# mini_exp_v1-1-0b.net
KiCad netlist of a schematic drawn in EAGLE
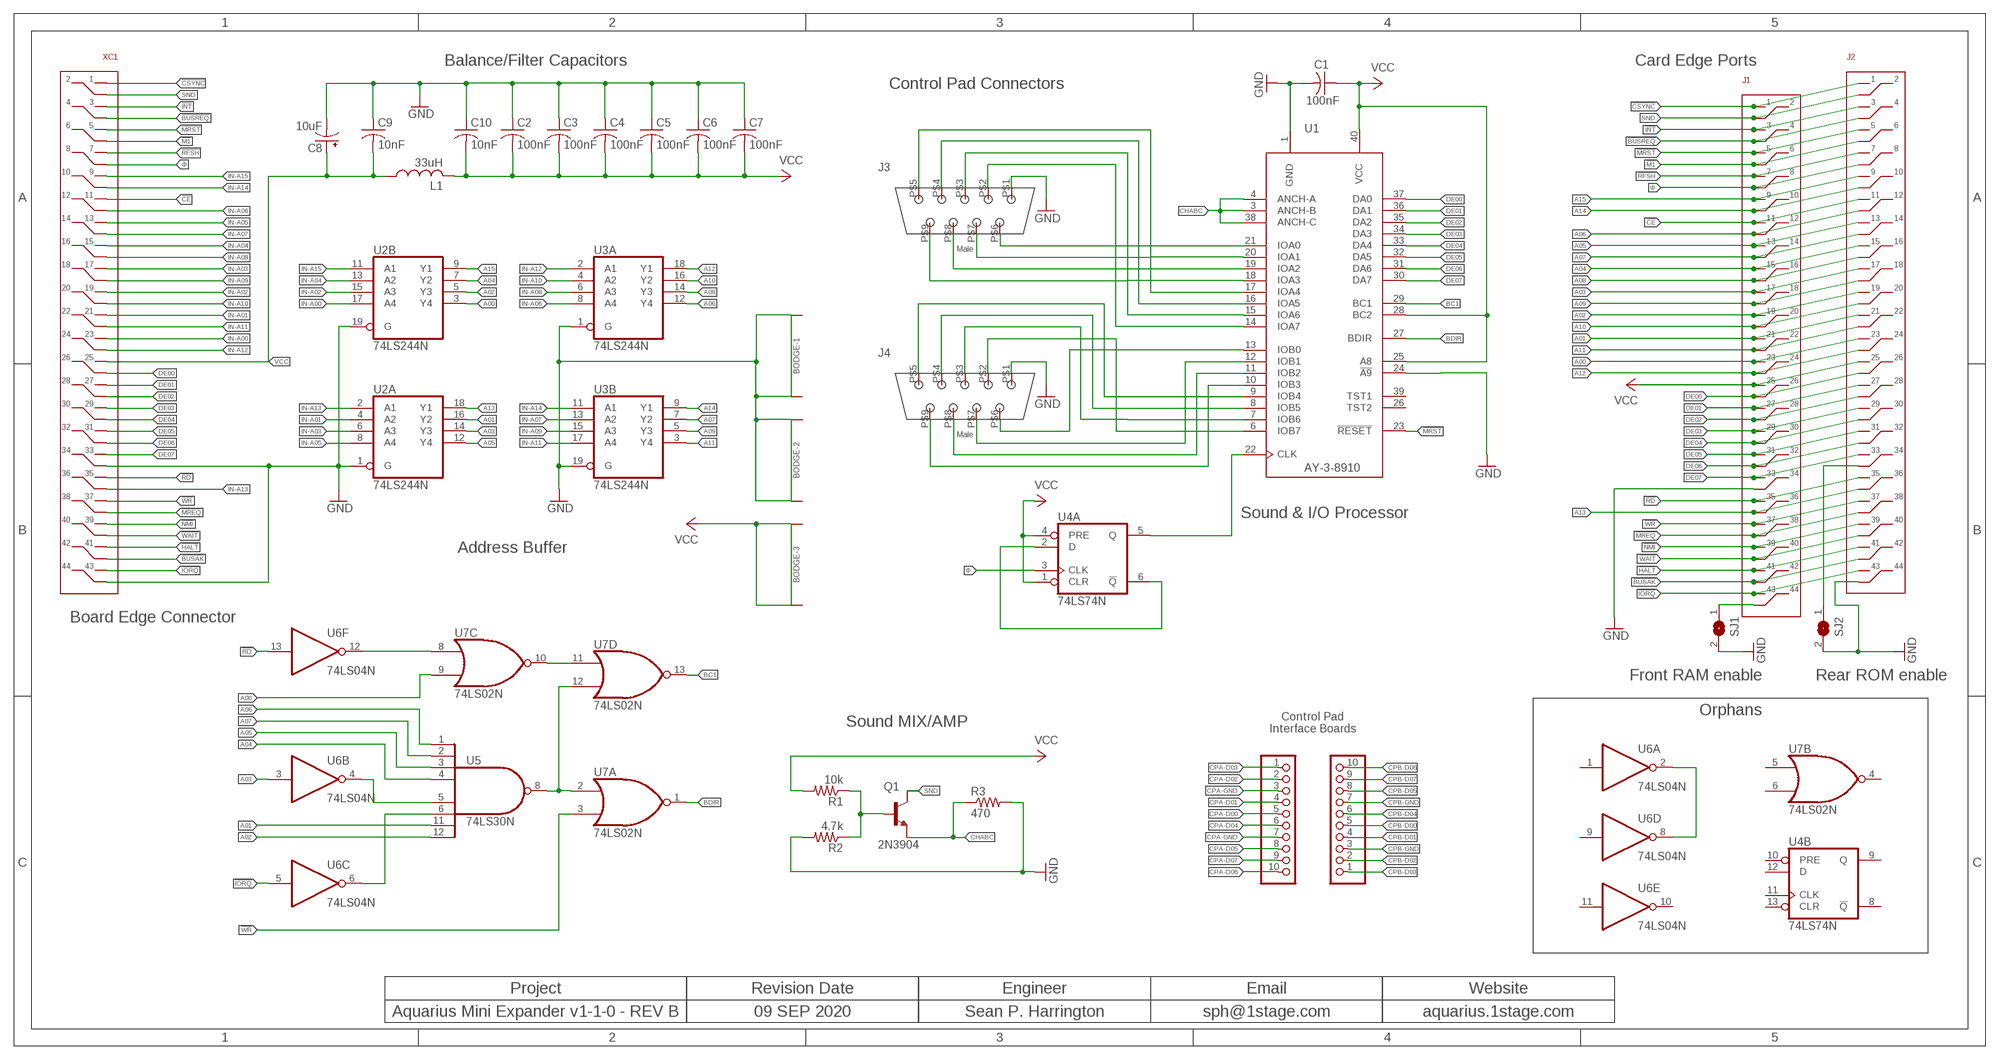
[diagram p0: schematic, sheet 1]

(export (version "E")
  (design (tool "Eeschema 10.0.6"))
  (components
    (comp (ref "C1")
      (value "100nF")
      (footprint "eagle-import:C050-025X095")
      (libsource (lib "eagle-import") (part "C-US050-025X095"))
    )
    (comp (ref "C2")
      (value "100nF")
      (footprint "eagle-import:C050-025X095")
      (libsource (lib "eagle-import") (part "C-US050-025X095"))
    )
    (comp (ref "C3")
      (value "100nF")
      (footprint "eagle-import:C050-025X095")
      (libsource (lib "eagle-import") (part "C-US050-025X095"))
    )
    (comp (ref "C4")
      (value "100nF")
      (footprint "eagle-import:C050-025X095")
      (libsource (lib "eagle-import") (part "C-US050-025X095"))
    )
    (comp (ref "C5")
      (value "100nF")
      (footprint "eagle-import:C050-025X095")
      (libsource (lib "eagle-import") (part "C-US050-025X095"))
    )
    (comp (ref "C6")
      (value "100nF")
      (footprint "eagle-import:C050-025X095")
      (libsource (lib "eagle-import") (part "C-US050-025X095"))
    )
    (comp (ref "C7")
      (value "100nF")
      (footprint "eagle-import:C050-025X095")
      (libsource (lib "eagle-import") (part "C-US050-025X095"))
    )
    (comp (ref "C8")
      (value "10uF")
      (footprint "eagle-import:E22-6")
      (libsource (lib "eagle-import") (part "CPOL-USE22-6AXIAL"))
    )
    (comp (ref "C9")
      (value "10nF")
      (footprint "eagle-import:C075-032X103")
      (libsource (lib "eagle-import") (part "C-US075-032X103"))
    )
    (comp (ref "C10")
      (value "10nF")
      (footprint "eagle-import:C075-032X103")
      (libsource (lib "eagle-import") (part "C-US075-032X103"))
    )
    (comp (ref "J1")
      (value "CR22A-44D-2.54DS(70)STRAIGHT")
      (footprint "eagle-import:CR22A-44D-2.54DS(70)")
      (libsource (lib "eagle-import") (part "CR22A-44D-2.54DS(70)STRAIGHT"))
    )
    (comp (ref "J2")
      (value "CR22A-44D-2.54DS(70)STRAIGHT")
      (footprint "eagle-import:CR22A-44D-2.54DS(70)")
      (libsource (lib "eagle-import") (part "CR22A-44D-2.54DS(70)STRAIGHT"))
    )
    (comp (ref "J3")
      (value "DB9-MALE-RA")
      (footprint "eagle-import:DB9-MALE-RA")
      (libsource (lib "eagle-import") (part "DB9-MALE-RA"))
    )
    (comp (ref "J4")
      (value "DB9-MALE-RA")
      (footprint "eagle-import:DB9-MALE-RA")
      (libsource (lib "eagle-import") (part "DB9-MALE-RA"))
    )
    (comp (ref "JP1")
      (value "PINHD-1X10")
      (footprint "eagle-import:1X10")
      (libsource (lib "eagle-import") (part "PINHD-1X10"))
    )
    (comp (ref "JP2")
      (value "PINHD-1X10")
      (footprint "eagle-import:1X10")
      (libsource (lib "eagle-import") (part "PINHD-1X10"))
    )
    (comp (ref "L1")
      (value "33uH")
      (footprint "eagle-import:0204_5")
      (libsource (lib "eagle-import") (part "L-US0204/5"))
    )
    (comp (ref "Q1")
      (value "2N3904")
      (footprint "eagle-import:TO92")
      (libsource (lib "eagle-import") (part "2N3904"))
    )
    (comp (ref "R1")
      (value "10k")
      (footprint "eagle-import:0207_7")
      (libsource (lib "eagle-import") (part "R-US_0207/7"))
    )
    (comp (ref "R2")
      (value "4.7k")
      (footprint "eagle-import:0207_7")
      (libsource (lib "eagle-import") (part "R-US_0207/7"))
    )
    (comp (ref "R3")
      (value "470")
      (footprint "eagle-import:0207_7")
      (libsource (lib "eagle-import") (part "R-US_0207/7"))
    )
    (comp (ref "SJ1") (value "SJ") (footprint "eagle-import:SJ") (libsource (lib "eagle-import") (part "SJ")))
    (comp (ref "SJ2") (value "SJ") (footprint "eagle-import:SJ") (libsource (lib "eagle-import") (part "SJ")))
    (comp (ref "U1")
      (value "AY-3-8910")
      (footprint "eagle-import:RAD38910-DIL40-6")
      (libsource (lib "eagle-import") (part "RAD38910DIL40-6"))
    )
    (comp (ref "U2")
      (value "74LS244N")
      (footprint "eagle-import:DIL20")
      (libsource (lib "eagle-import") (part "74244NLS"))
    )
    (comp (ref "U3")
      (value "74LS244N")
      (footprint "eagle-import:DIL20")
      (libsource (lib "eagle-import") (part "74244NLS"))
    )
    (comp (ref "U4")
      (value "74LS74N")
      (footprint "eagle-import:DIL14")
      (libsource (lib "eagle-import") (part "7474NLS"))
    )
    (comp (ref "U5")
      (value "74LS30N")
      (footprint "eagle-import:DIL14")
      (libsource (lib "eagle-import") (part "7430NLS"))
    )
    (comp (ref "U6")
      (value "74LS04N")
      (footprint "eagle-import:DIL14")
      (libsource (lib "eagle-import") (part "7404NLS"))
    )
    (comp (ref "U7")
      (value "74LS02N")
      (footprint "eagle-import:DIL14")
      (libsource (lib "eagle-import") (part "7402NLS"))
    )
    (comp (ref "XC1")
      (value "AQ-CART-EDGE")
      (footprint "eagle-import:AQ-CART-EDGE")
      (libsource (lib "eagle-import") (part "AQ-CART-EDGE"))
    )
    (comp (ref "XX01")
      (value "AQ-MX-BODGE-1")
      (footprint "eagle-import:AQ-MX-BODGE-1")
      (libsource (lib "eagle-import") (part "AQ-MX-BODGE-1"))
    )
    (comp (ref "XX02")
      (value "AQ-MX-BODGE-2")
      (footprint "eagle-import:AQ-MX-BODGE-2")
      (libsource (lib "eagle-import") (part "AQ-MX-BODGE-2"))
    )
    (comp (ref "XX03")
      (value "AQ-MX-BODGE-3")
      (footprint "eagle-import:AQ-MX-BODGE-3")
      (libsource (lib "eagle-import") (part "AQ-MX-BODGE-3"))
    )
  )
  (nets
    (net (code "1") (name "/~{BUSAK}") (class "Default")
      (node (ref "J1") (pin "P$42") (pinfunction "X42_P$42") (pintype "bidirectional"))
      (node (ref "J2") (pin "P$42") (pinfunction "X42_P$42") (pintype "bidirectional"))
      (node (ref "XC1") (pin "P$42") (pinfunction "X42_P$42") (pintype "bidirectional"))
    )
    (net (code "2") (name "/~{BUSREQ}") (class "Default")
      (node (ref "J1") (pin "P$4") (pinfunction "X4_P$4") (pintype "bidirectional"))
      (node (ref "J2") (pin "P$4") (pinfunction "X4_P$4") (pintype "bidirectional"))
      (node (ref "XC1") (pin "P$4") (pinfunction "X4_P$4") (pintype "bidirectional"))
    )
    (net (code "3") (name "/~{CE}") (class "Default")
      (node (ref "J1") (pin "P$11") (pinfunction "X11_P$11") (pintype "bidirectional"))
      (node (ref "J2") (pin "P$11") (pinfunction "X11_P$11") (pintype "bidirectional"))
      (node (ref "XC1") (pin "P$11") (pinfunction "X11_P$11") (pintype "bidirectional"))
    )
    (net (code "4") (name "/~{CSYNC}") (class "Default")
      (node (ref "J1") (pin "P$1") (pinfunction "X1_P$1") (pintype "bidirectional"))
      (node (ref "J2") (pin "P$1") (pinfunction "X1_P$1") (pintype "bidirectional"))
      (node (ref "XC1") (pin "P$1") (pinfunction "X1_P$1") (pintype "bidirectional"))
    )
    (net (code "5") (name "/~{HALT}") (class "Default")
      (node (ref "J1") (pin "P$41") (pinfunction "X41_P$41") (pintype "bidirectional"))
      (node (ref "J2") (pin "P$41") (pinfunction "X41_P$41") (pintype "bidirectional"))
      (node (ref "XC1") (pin "P$41") (pinfunction "X41_P$41") (pintype "bidirectional"))
    )
    (net (code "6") (name "/~{INT}") (class "Default")
      (node (ref "J1") (pin "P$3") (pinfunction "X3_P$3") (pintype "bidirectional"))
      (node (ref "J2") (pin "P$3") (pinfunction "X3_P$3") (pintype "bidirectional"))
      (node (ref "XC1") (pin "P$3") (pinfunction "X3_P$3") (pintype "bidirectional"))
    )
    (net (code "7") (name "/~{IORQ}") (class "Default")
      (node (ref "J1") (pin "P$43") (pinfunction "X43_P$43") (pintype "bidirectional"))
      (node (ref "J2") (pin "P$43") (pinfunction "X43_P$43") (pintype "bidirectional"))
      (node (ref "U6") (pin "5") (pinfunction "I_5") (pintype "input"))
      (node (ref "XC1") (pin "P$43") (pinfunction "X43_P$43") (pintype "bidirectional"))
    )
    (net (code "8") (name "/~{M1}") (class "Default")
      (node (ref "J1") (pin "P$6") (pinfunction "X6_P$6") (pintype "bidirectional"))
      (node (ref "J2") (pin "P$6") (pinfunction "X6_P$6") (pintype "bidirectional"))
      (node (ref "XC1") (pin "P$6") (pinfunction "X6_P$6") (pintype "bidirectional"))
    )
    (net (code "9") (name "/~{MREQ}") (class "Default")
      (node (ref "J1") (pin "P$38") (pinfunction "X38_P$38") (pintype "bidirectional"))
      (node (ref "J2") (pin "P$38") (pinfunction "X38_P$38") (pintype "bidirectional"))
      (node (ref "XC1") (pin "P$38") (pinfunction "X38_P$38") (pintype "bidirectional"))
    )
    (net (code "10") (name "/~{MRST}") (class "Default")
      (node (ref "J1") (pin "P$5") (pinfunction "X5_P$5") (pintype "bidirectional"))
      (node (ref "J2") (pin "P$5") (pinfunction "X5_P$5") (pintype "bidirectional"))
      (node (ref "U1") (pin "23") (pinfunction "~{RESET}_23") (pintype "bidirectional"))
      (node (ref "XC1") (pin "P$5") (pinfunction "X5_P$5") (pintype "bidirectional"))
    )
    (net (code "11") (name "/~{NMI}") (class "Default")
      (node (ref "J1") (pin "P$39") (pinfunction "X39_P$39") (pintype "bidirectional"))
      (node (ref "J2") (pin "P$39") (pinfunction "X39_P$39") (pintype "bidirectional"))
      (node (ref "XC1") (pin "P$39") (pinfunction "X39_P$39") (pintype "bidirectional"))
    )
    (net (code "12") (name "/~{RD}") (class "Default")
      (node (ref "J1") (pin "P$35") (pinfunction "X35_P$35") (pintype "bidirectional"))
      (node (ref "J2") (pin "P$35") (pinfunction "X35_P$35") (pintype "bidirectional"))
      (node (ref "U6") (pin "13") (pinfunction "I_13") (pintype "input"))
      (node (ref "XC1") (pin "P$35") (pinfunction "X35_P$35") (pintype "bidirectional"))
    )
    (net (code "13") (name "/~{RFSH}") (class "Default")
      (node (ref "J1") (pin "P$7") (pinfunction "X7_P$7") (pintype "bidirectional"))
      (node (ref "J2") (pin "P$7") (pinfunction "X7_P$7") (pintype "bidirectional"))
      (node (ref "XC1") (pin "P$7") (pinfunction "X7_P$7") (pintype "bidirectional"))
    )
    (net (code "14") (name "/~{WAIT}") (class "Default")
      (node (ref "J1") (pin "P$40") (pinfunction "X40_P$40") (pintype "bidirectional"))
      (node (ref "J2") (pin "P$40") (pinfunction "X40_P$40") (pintype "bidirectional"))
      (node (ref "XC1") (pin "P$40") (pinfunction "X40_P$40") (pintype "bidirectional"))
    )
    (net (code "15") (name "/~{WR}") (class "Default")
      (node (ref "J1") (pin "P$37") (pinfunction "X37_P$37") (pintype "bidirectional"))
      (node (ref "J2") (pin "P$37") (pinfunction "X37_P$37") (pintype "bidirectional"))
      (node (ref "U7") (pin "3") (pinfunction "I1_3") (pintype "input"))
      (node (ref "XC1") (pin "P$37") (pinfunction "X37_P$37") (pintype "bidirectional"))
    )
    (net (code "16") (name "A00") (class "Default")
      (node (ref "J1") (pin "P$23") (pinfunction "X23_P$23") (pintype "bidirectional"))
      (node (ref "J2") (pin "P$23") (pinfunction "X23_P$23") (pintype "bidirectional"))
      (node (ref "U2") (pin "3") (pinfunction "Y4_3") (pintype "tri_state"))
      (node (ref "U7") (pin "9") (pinfunction "I1_9") (pintype "input"))
    )
    (net (code "17") (name "A01") (class "Default")
      (node (ref "J1") (pin "P$21") (pinfunction "X21_P$21") (pintype "bidirectional"))
      (node (ref "J2") (pin "P$21") (pinfunction "X21_P$21") (pintype "bidirectional"))
      (node (ref "U2") (pin "16") (pinfunction "Y2_16") (pintype "tri_state"))
      (node (ref "U5") (pin "11") (pinfunction "I6_11") (pintype "input"))
    )
    (net (code "18") (name "A02") (class "Default")
      (node (ref "J1") (pin "P$19") (pinfunction "X19_P$19") (pintype "bidirectional"))
      (node (ref "J2") (pin "P$19") (pinfunction "X19_P$19") (pintype "bidirectional"))
      (node (ref "U2") (pin "5") (pinfunction "Y3_5") (pintype "tri_state"))
      (node (ref "U5") (pin "12") (pinfunction "I7_12") (pintype "input"))
    )
    (net (code "19") (name "A03") (class "Default")
      (node (ref "J1") (pin "P$17") (pinfunction "X17_P$17") (pintype "bidirectional"))
      (node (ref "J2") (pin "P$17") (pinfunction "X17_P$17") (pintype "bidirectional"))
      (node (ref "U2") (pin "14") (pinfunction "Y3_14") (pintype "tri_state"))
      (node (ref "U6") (pin "3") (pinfunction "I_3") (pintype "input"))
    )
    (net (code "20") (name "A04") (class "Default")
      (node (ref "J1") (pin "P$15") (pinfunction "X15_P$15") (pintype "bidirectional"))
      (node (ref "J2") (pin "P$15") (pinfunction "X15_P$15") (pintype "bidirectional"))
      (node (ref "U2") (pin "7") (pinfunction "Y2_7") (pintype "tri_state"))
      (node (ref "U5") (pin "4") (pinfunction "I3_4") (pintype "input"))
    )
    (net (code "21") (name "A05") (class "Default")
      (node (ref "J1") (pin "P$13") (pinfunction "X13_P$13") (pintype "bidirectional"))
      (node (ref "J2") (pin "P$13") (pinfunction "X13_P$13") (pintype "bidirectional"))
      (node (ref "U2") (pin "12") (pinfunction "Y4_12") (pintype "tri_state"))
      (node (ref "U5") (pin "3") (pinfunction "I2_3") (pintype "input"))
    )
    (net (code "22") (name "A06") (class "Default")
      (node (ref "J1") (pin "P$12") (pinfunction "X12_P$12") (pintype "bidirectional"))
      (node (ref "J2") (pin "P$12") (pinfunction "X12_P$12") (pintype "bidirectional"))
      (node (ref "U3") (pin "12") (pinfunction "Y4_12") (pintype "tri_state"))
      (node (ref "U5") (pin "1") (pinfunction "I0_1") (pintype "input"))
    )
    (net (code "23") (name "A07") (class "Default")
      (node (ref "J1") (pin "P$14") (pinfunction "X14_P$14") (pintype "bidirectional"))
      (node (ref "J2") (pin "P$14") (pinfunction "X14_P$14") (pintype "bidirectional"))
      (node (ref "U3") (pin "7") (pinfunction "Y2_7") (pintype "tri_state"))
      (node (ref "U5") (pin "2") (pinfunction "I1_2") (pintype "input"))
    )
    (net (code "24") (name "A08") (class "Default")
      (node (ref "J1") (pin "P$16") (pinfunction "X16_P$16") (pintype "bidirectional"))
      (node (ref "J2") (pin "P$16") (pinfunction "X16_P$16") (pintype "bidirectional"))
      (node (ref "U3") (pin "14") (pinfunction "Y3_14") (pintype "tri_state"))
    )
    (net (code "25") (name "A09") (class "Default")
      (node (ref "J1") (pin "P$18") (pinfunction "X18_P$18") (pintype "bidirectional"))
      (node (ref "J2") (pin "P$18") (pinfunction "X18_P$18") (pintype "bidirectional"))
      (node (ref "U3") (pin "5") (pinfunction "Y3_5") (pintype "tri_state"))
    )
    (net (code "26") (name "A10") (class "Default")
      (node (ref "J1") (pin "P$20") (pinfunction "X20_P$20") (pintype "bidirectional"))
      (node (ref "J2") (pin "P$20") (pinfunction "X20_P$20") (pintype "bidirectional"))
      (node (ref "U3") (pin "16") (pinfunction "Y2_16") (pintype "tri_state"))
    )
    (net (code "27") (name "A11") (class "Default")
      (node (ref "J1") (pin "P$22") (pinfunction "X22_P$22") (pintype "bidirectional"))
      (node (ref "J2") (pin "P$22") (pinfunction "X22_P$22") (pintype "bidirectional"))
      (node (ref "U3") (pin "3") (pinfunction "Y4_3") (pintype "tri_state"))
    )
    (net (code "28") (name "A12") (class "Default")
      (node (ref "J1") (pin "P$24") (pinfunction "X24_P$24") (pintype "bidirectional"))
      (node (ref "J2") (pin "P$24") (pinfunction "X24_P$24") (pintype "bidirectional"))
      (node (ref "U3") (pin "18") (pinfunction "Y1_18") (pintype "tri_state"))
    )
    (net (code "29") (name "A13") (class "Default")
      (node (ref "J1") (pin "P$36") (pinfunction "X36_P$36") (pintype "bidirectional"))
      (node (ref "J2") (pin "P$36") (pinfunction "X36_P$36") (pintype "bidirectional"))
      (node (ref "U2") (pin "18") (pinfunction "Y1_18") (pintype "tri_state"))
    )
    (net (code "30") (name "A14") (class "Default")
      (node (ref "J1") (pin "P$10") (pinfunction "X10_P$10") (pintype "bidirectional"))
      (node (ref "J2") (pin "P$10") (pinfunction "X10_P$10") (pintype "bidirectional"))
      (node (ref "U3") (pin "9") (pinfunction "Y1_9") (pintype "tri_state"))
    )
    (net (code "31") (name "A15") (class "Default")
      (node (ref "J1") (pin "P$9") (pinfunction "X9_P$9") (pintype "bidirectional"))
      (node (ref "J2") (pin "P$9") (pinfunction "X9_P$9") (pintype "bidirectional"))
      (node (ref "U2") (pin "9") (pinfunction "Y1_9") (pintype "tri_state"))
    )
    (net (code "32") (name "BC1") (class "Default")
      (node (ref "U1") (pin "29") (pinfunction "BC1_29") (pintype "bidirectional"))
      (node (ref "U7") (pin "13") (pinfunction "O_13") (pintype "output"))
    )
    (net (code "33") (name "BDIR") (class "Default")
      (node (ref "U1") (pin "27") (pinfunction "BDIR_27") (pintype "bidirectional"))
      (node (ref "U7") (pin "1") (pinfunction "O_1") (pintype "output"))
    )
    (net (code "34") (name "CHABC") (class "Default")
      (node (ref "Q1") (pin "3") (pinfunction "E_3") (pintype "passive"))
      (node (ref "R3") (pin "1") (pinfunction "1_1") (pintype "passive"))
      (node (ref "U1") (pin "3") (pinfunction "ANCH-B_3") (pintype "bidirectional"))
      (node (ref "U1") (pin "38") (pinfunction "ANCH-C_38") (pintype "bidirectional"))
      (node (ref "U1") (pin "4") (pinfunction "ANCH-A_4") (pintype "bidirectional"))
    )
    (net (code "35") (name "CPA-D00") (class "Default")
      (node (ref "JP1") (pin "5") (pinfunction "5_5") (pintype "passive"))
    )
    (net (code "36") (name "CPA-D01") (class "Default")
      (node (ref "JP1") (pin "4") (pinfunction "4_4") (pintype "passive"))
    )
    (net (code "37") (name "CPA-D02") (class "Default")
      (node (ref "JP1") (pin "2") (pinfunction "2_2") (pintype "passive"))
    )
    (net (code "38") (name "CPA-D03") (class "Default")
      (node (ref "JP1") (pin "1") (pinfunction "1_1") (pintype "passive"))
    )
    (net (code "39") (name "CPA-D04") (class "Default")
      (node (ref "JP1") (pin "6") (pinfunction "6_6") (pintype "passive"))
    )
    (net (code "40") (name "CPA-D05") (class "Default")
      (node (ref "JP1") (pin "8") (pinfunction "8_8") (pintype "passive"))
    )
    (net (code "41") (name "CPA-D06") (class "Default")
      (node (ref "JP1") (pin "10") (pinfunction "10_10") (pintype "passive"))
    )
    (net (code "42") (name "CPA-D07") (class "Default")
      (node (ref "JP1") (pin "9") (pinfunction "9_9") (pintype "passive"))
    )
    (net (code "43") (name "CPA-GND") (class "Default")
      (node (ref "JP1") (pin "3") (pinfunction "3_3") (pintype "passive"))
      (node (ref "JP1") (pin "7") (pinfunction "7_7") (pintype "passive"))
    )
    (net (code "44") (name "CPB-D00") (class "Default")
      (node (ref "JP2") (pin "5") (pinfunction "5_5") (pintype "passive"))
    )
    (net (code "45") (name "CPB-D01") (class "Default")
      (node (ref "JP2") (pin "4") (pinfunction "4_4") (pintype "passive"))
    )
    (net (code "46") (name "CPB-D02") (class "Default")
      (node (ref "JP2") (pin "2") (pinfunction "2_2") (pintype "passive"))
    )
    (net (code "47") (name "CPB-D03") (class "Default")
      (node (ref "JP2") (pin "1") (pinfunction "1_1") (pintype "passive"))
    )
    (net (code "48") (name "CPB-D04") (class "Default")
      (node (ref "JP2") (pin "6") (pinfunction "6_6") (pintype "passive"))
    )
    (net (code "49") (name "CPB-D05") (class "Default")
      (node (ref "JP2") (pin "8") (pinfunction "8_8") (pintype "passive"))
    )
    (net (code "50") (name "CPB-D06") (class "Default")
      (node (ref "JP2") (pin "10") (pinfunction "10_10") (pintype "passive"))
    )
    (net (code "51") (name "CPB-D07") (class "Default")
      (node (ref "JP2") (pin "9") (pinfunction "9_9") (pintype "passive"))
    )
    (net (code "52") (name "CPB-GND") (class "Default")
      (node (ref "JP2") (pin "3") (pinfunction "3_3") (pintype "passive"))
      (node (ref "JP2") (pin "7") (pinfunction "7_7") (pintype "passive"))
    )
    (net (code "53") (name "DE00") (class "Default")
      (node (ref "J1") (pin "P$26") (pinfunction "X26_P$26") (pintype "bidirectional"))
      (node (ref "J2") (pin "P$26") (pinfunction "X26_P$26") (pintype "bidirectional"))
      (node (ref "U1") (pin "37") (pinfunction "DA0_37") (pintype "bidirectional"))
      (node (ref "XC1") (pin "P$26") (pinfunction "X26_P$26") (pintype "bidirectional"))
    )
    (net (code "54") (name "DE01") (class "Default")
      (node (ref "J1") (pin "P$27") (pinfunction "X27_P$27") (pintype "bidirectional"))
      (node (ref "J2") (pin "P$27") (pinfunction "X27_P$27") (pintype "bidirectional"))
      (node (ref "U1") (pin "36") (pinfunction "DA1_36") (pintype "bidirectional"))
      (node (ref "XC1") (pin "P$27") (pinfunction "X27_P$27") (pintype "bidirectional"))
    )
    (net (code "55") (name "DE02") (class "Default")
      (node (ref "J1") (pin "P$28") (pinfunction "X28_P$28") (pintype "bidirectional"))
      (node (ref "J2") (pin "P$28") (pinfunction "X28_P$28") (pintype "bidirectional"))
      (node (ref "U1") (pin "35") (pinfunction "DA2_35") (pintype "bidirectional"))
      (node (ref "XC1") (pin "P$28") (pinfunction "X28_P$28") (pintype "bidirectional"))
    )
    (net (code "56") (name "DE03") (class "Default")
      (node (ref "J1") (pin "P$29") (pinfunction "X29_P$29") (pintype "bidirectional"))
      (node (ref "J2") (pin "P$29") (pinfunction "X29_P$29") (pintype "bidirectional"))
      (node (ref "U1") (pin "34") (pinfunction "DA3_34") (pintype "bidirectional"))
      (node (ref "XC1") (pin "P$29") (pinfunction "X29_P$29") (pintype "bidirectional"))
    )
    (net (code "57") (name "DE04") (class "Default")
      (node (ref "J1") (pin "P$30") (pinfunction "X30_P$30") (pintype "bidirectional"))
      (node (ref "J2") (pin "P$30") (pinfunction "X30_P$30") (pintype "bidirectional"))
      (node (ref "U1") (pin "33") (pinfunction "DA4_33") (pintype "bidirectional"))
      (node (ref "XC1") (pin "P$30") (pinfunction "X30_P$30") (pintype "bidirectional"))
    )
    (net (code "58") (name "DE05") (class "Default")
      (node (ref "J1") (pin "P$31") (pinfunction "X31_P$31") (pintype "bidirectional"))
      (node (ref "J2") (pin "P$31") (pinfunction "X31_P$31") (pintype "bidirectional"))
      (node (ref "U1") (pin "32") (pinfunction "DA5_32") (pintype "bidirectional"))
      (node (ref "XC1") (pin "P$31") (pinfunction "X31_P$31") (pintype "bidirectional"))
    )
    (net (code "59") (name "DE06") (class "Default")
      (node (ref "J1") (pin "P$32") (pinfunction "X32_P$32") (pintype "bidirectional"))
      (node (ref "J2") (pin "P$32") (pinfunction "X32_P$32") (pintype "bidirectional"))
      (node (ref "U1") (pin "31") (pinfunction "DA6_31") (pintype "bidirectional"))
      (node (ref "XC1") (pin "P$32") (pinfunction "X32_P$32") (pintype "bidirectional"))
    )
    (net (code "60") (name "DE07") (class "Default")
      (node (ref "J1") (pin "P$33") (pinfunction "X33_P$33") (pintype "bidirectional"))
      (node (ref "J2") (pin "P$33") (pinfunction "X33_P$33") (pintype "bidirectional"))
      (node (ref "U1") (pin "30") (pinfunction "DA7_30") (pintype "bidirectional"))
      (node (ref "XC1") (pin "P$33") (pinfunction "X33_P$33") (pintype "bidirectional"))
    )
    (net (code "61") (name "GND") (class "Default")
      (node (ref "C1") (pin "2") (pinfunction "2_2") (pintype "passive"))
      (node (ref "C10") (pin "1") (pinfunction "1_1") (pintype "passive"))
      (node (ref "C2") (pin "1") (pinfunction "1_1") (pintype "passive"))
      (node (ref "C3") (pin "1") (pinfunction "1_1") (pintype "passive"))
      (node (ref "C4") (pin "1") (pinfunction "1_1") (pintype "passive"))
      (node (ref "C5") (pin "1") (pinfunction "1_1") (pintype "passive"))
      (node (ref "C6") (pin "1") (pinfunction "1_1") (pintype "passive"))
      (node (ref "C7") (pin "1") (pinfunction "1_1") (pintype "passive"))
      (node (ref "C8") (pin "-") (pinfunction "-_-") (pintype "passive"))
      (node (ref "C9") (pin "1") (pinfunction "1_1") (pintype "passive"))
      (node (ref "J1") (pin "P$34") (pinfunction "X34_P$34") (pintype "bidirectional"))
      (node (ref "J2") (pin "P$44") (pinfunction "X44_P$44") (pintype "bidirectional"))
      (node (ref "J3") (pin "P$1") (pinfunction "P$1_P$1") (pintype "bidirectional"))
      (node (ref "J4") (pin "P$1") (pinfunction "P$1_P$1") (pintype "bidirectional"))
      (node (ref "R2") (pin "2") (pinfunction "2_2") (pintype "passive"))
      (node (ref "R3") (pin "2") (pinfunction "2_2") (pintype "passive"))
      (node (ref "SJ1") (pin "2") (pinfunction "2_2") (pintype "passive"))
      (node (ref "SJ2") (pin "2") (pinfunction "2_2") (pintype "passive"))
      (node (ref "U1") (pin "1") (pinfunction "GND_1") (pintype "power_in"))
      (node (ref "U1") (pin "24") (pinfunction "~{A9}_24") (pintype "bidirectional"))
      (node (ref "U2") (pin "1") (pinfunction "G_1") (pintype "input"))
      (node (ref "U2") (pin "19") (pinfunction "G_19") (pintype "input"))
      (node (ref "U3") (pin "1") (pinfunction "G_1") (pintype "input"))
      (node (ref "U3") (pin "19") (pinfunction "G_19") (pintype "input"))
      (node (ref "XC1") (pin "P$34") (pinfunction "X34_P$34") (pintype "bidirectional"))
      (node (ref "XC1") (pin "P$44") (pinfunction "X44_P$44") (pintype "bidirectional"))
      (node (ref "XX01") (pin "P$1") (pinfunction "P$1_P$1") (pintype "bidirectional"))
      (node (ref "XX01") (pin "P$2") (pinfunction "P$2_P$2") (pintype "bidirectional"))
      (node (ref "XX02") (pin "P$1") (pinfunction "P$1_P$1") (pintype "bidirectional"))
      (node (ref "XX02") (pin "P$2") (pinfunction "P$2_P$2") (pintype "bidirectional"))
    )
    (net (code "62") (name "IN-A00") (class "Default")
      (node (ref "U2") (pin "17") (pinfunction "A4_17") (pintype "input"))
      (node (ref "XC1") (pin "P$23") (pinfunction "X23_P$23") (pintype "bidirectional"))
    )
    (net (code "63") (name "IN-A01") (class "Default")
      (node (ref "U2") (pin "4") (pinfunction "A2_4") (pintype "input"))
      (node (ref "XC1") (pin "P$21") (pinfunction "X21_P$21") (pintype "bidirectional"))
    )
    (net (code "64") (name "IN-A02") (class "Default")
      (node (ref "U2") (pin "15") (pinfunction "A3_15") (pintype "input"))
      (node (ref "XC1") (pin "P$19") (pinfunction "X19_P$19") (pintype "bidirectional"))
    )
    (net (code "65") (name "IN-A03") (class "Default")
      (node (ref "U2") (pin "6") (pinfunction "A3_6") (pintype "input"))
      (node (ref "XC1") (pin "P$17") (pinfunction "X17_P$17") (pintype "bidirectional"))
    )
    (net (code "66") (name "IN-A04") (class "Default")
      (node (ref "U2") (pin "13") (pinfunction "A2_13") (pintype "input"))
      (node (ref "XC1") (pin "P$15") (pinfunction "X15_P$15") (pintype "bidirectional"))
    )
    (net (code "67") (name "IN-A05") (class "Default")
      (node (ref "U2") (pin "8") (pinfunction "A4_8") (pintype "input"))
      (node (ref "XC1") (pin "P$13") (pinfunction "X13_P$13") (pintype "bidirectional"))
    )
    (net (code "68") (name "IN-A06") (class "Default")
      (node (ref "U3") (pin "8") (pinfunction "A4_8") (pintype "input"))
      (node (ref "XC1") (pin "P$12") (pinfunction "X12_P$12") (pintype "bidirectional"))
    )
    (net (code "69") (name "IN-A07") (class "Default")
      (node (ref "U3") (pin "13") (pinfunction "A2_13") (pintype "input"))
      (node (ref "XC1") (pin "P$14") (pinfunction "X14_P$14") (pintype "bidirectional"))
    )
    (net (code "70") (name "IN-A08") (class "Default")
      (node (ref "U3") (pin "6") (pinfunction "A3_6") (pintype "input"))
      (node (ref "XC1") (pin "P$16") (pinfunction "X16_P$16") (pintype "bidirectional"))
    )
    (net (code "71") (name "IN-A09") (class "Default")
      (node (ref "U3") (pin "15") (pinfunction "A3_15") (pintype "input"))
      (node (ref "XC1") (pin "P$18") (pinfunction "X18_P$18") (pintype "bidirectional"))
    )
    (net (code "72") (name "IN-A10") (class "Default")
      (node (ref "U3") (pin "4") (pinfunction "A2_4") (pintype "input"))
      (node (ref "XC1") (pin "P$20") (pinfunction "X20_P$20") (pintype "bidirectional"))
    )
    (net (code "73") (name "IN-A11") (class "Default")
      (node (ref "U3") (pin "17") (pinfunction "A4_17") (pintype "input"))
      (node (ref "XC1") (pin "P$22") (pinfunction "X22_P$22") (pintype "bidirectional"))
    )
    (net (code "74") (name "IN-A12") (class "Default")
      (node (ref "U3") (pin "2") (pinfunction "A1_2") (pintype "input"))
      (node (ref "XC1") (pin "P$24") (pinfunction "X24_P$24") (pintype "bidirectional"))
    )
    (net (code "75") (name "IN-A13") (class "Default")
      (node (ref "U2") (pin "2") (pinfunction "A1_2") (pintype "input"))
      (node (ref "XC1") (pin "P$36") (pinfunction "X36_P$36") (pintype "bidirectional"))
    )
    (net (code "76") (name "IN-A14") (class "Default")
      (node (ref "U3") (pin "11") (pinfunction "A1_11") (pintype "input"))
      (node (ref "XC1") (pin "P$10") (pinfunction "X10_P$10") (pintype "bidirectional"))
    )
    (net (code "77") (name "IN-A15") (class "Default")
      (node (ref "U2") (pin "11") (pinfunction "A1_11") (pintype "input"))
      (node (ref "XC1") (pin "P$9") (pinfunction "X9_P$9") (pintype "bidirectional"))
    )
    (net (code "78") (name "Net-(J1-X44)") (class "Default")
      (node (ref "J1") (pin "P$44") (pinfunction "X44_P$44") (pintype "bidirectional"))
      (node (ref "SJ1") (pin "1") (pinfunction "1_1") (pintype "passive"))
    )
    (net (code "79") (name "Net-(J2-X34)") (class "Default")
      (node (ref "J2") (pin "P$34") (pinfunction "X34_P$34") (pintype "bidirectional"))
      (node (ref "SJ2") (pin "1") (pinfunction "1_1") (pintype "passive"))
    )
    (net (code "80") (name "Net-(Q1-B)") (class "Default")
      (node (ref "Q1") (pin "2") (pinfunction "B_2") (pintype "passive"))
      (node (ref "R1") (pin "1") (pinfunction "1_1") (pintype "passive"))
      (node (ref "R2") (pin "1") (pinfunction "1_1") (pintype "passive"))
    )
    (net (code "81") (name "Net-(U1-CLK)") (class "Default")
      (node (ref "U1") (pin "22") (pinfunction "CLK_22") (pintype "input"))
      (node (ref "U4") (pin "5") (pinfunction "Q_5") (pintype "output"))
    )
    (net (code "82") (name "Net-(U1-IOA0)") (class "Default")
      (node (ref "J3") (pin "P$6") (pinfunction "P$6_P$6") (pintype "bidirectional"))
      (node (ref "U1") (pin "21") (pinfunction "IOA0_21") (pintype "bidirectional"))
    )
    (net (code "83") (name "Net-(U1-IOA1)") (class "Default")
      (node (ref "J3") (pin "P$7") (pinfunction "P$7_P$7") (pintype "bidirectional"))
      (node (ref "U1") (pin "20") (pinfunction "IOA1_20") (pintype "bidirectional"))
    )
    (net (code "84") (name "Net-(U1-IOA2)") (class "Default")
      (node (ref "J3") (pin "P$8") (pinfunction "P$8_P$8") (pintype "bidirectional"))
      (node (ref "U1") (pin "19") (pinfunction "IOA2_19") (pintype "bidirectional"))
    )
    (net (code "85") (name "Net-(U1-IOA3)") (class "Default")
      (node (ref "J3") (pin "P$9") (pinfunction "P$9_P$9") (pintype "bidirectional"))
      (node (ref "U1") (pin "18") (pinfunction "IOA3_18") (pintype "bidirectional"))
    )
    (net (code "86") (name "Net-(U1-IOA4)") (class "Default")
      (node (ref "J3") (pin "P$5") (pinfunction "P$5_P$5") (pintype "bidirectional"))
      (node (ref "U1") (pin "17") (pinfunction "IOA4_17") (pintype "bidirectional"))
    )
    (net (code "87") (name "Net-(U1-IOA5)") (class "Default")
      (node (ref "J3") (pin "P$4") (pinfunction "P$4_P$4") (pintype "bidirectional"))
      (node (ref "U1") (pin "16") (pinfunction "IOA5_16") (pintype "bidirectional"))
    )
    (net (code "88") (name "Net-(U1-IOA6)") (class "Default")
      (node (ref "J3") (pin "P$3") (pinfunction "P$3_P$3") (pintype "bidirectional"))
      (node (ref "U1") (pin "15") (pinfunction "IOA6_15") (pintype "bidirectional"))
    )
    (net (code "89") (name "Net-(U1-IOA7)") (class "Default")
      (node (ref "J3") (pin "P$2") (pinfunction "P$2_P$2") (pintype "bidirectional"))
      (node (ref "U1") (pin "14") (pinfunction "IOA7_14") (pintype "bidirectional"))
    )
    (net (code "90") (name "Net-(U1-IOB0)") (class "Default")
      (node (ref "J4") (pin "P$6") (pinfunction "P$6_P$6") (pintype "bidirectional"))
      (node (ref "U1") (pin "13") (pinfunction "IOB0_13") (pintype "bidirectional"))
    )
    (net (code "91") (name "Net-(U1-IOB1)") (class "Default")
      (node (ref "J4") (pin "P$7") (pinfunction "P$7_P$7") (pintype "bidirectional"))
      (node (ref "U1") (pin "12") (pinfunction "IOB1_12") (pintype "bidirectional"))
    )
    (net (code "92") (name "Net-(U1-IOB2)") (class "Default")
      (node (ref "J4") (pin "P$8") (pinfunction "P$8_P$8") (pintype "bidirectional"))
      (node (ref "U1") (pin "11") (pinfunction "IOB2_11") (pintype "bidirectional"))
    )
    (net (code "93") (name "Net-(U1-IOB3)") (class "Default")
      (node (ref "J4") (pin "P$9") (pinfunction "P$9_P$9") (pintype "bidirectional"))
      (node (ref "U1") (pin "10") (pinfunction "IOB3_10") (pintype "bidirectional"))
    )
    (net (code "94") (name "Net-(U1-IOB4)") (class "Default")
      (node (ref "J4") (pin "P$5") (pinfunction "P$5_P$5") (pintype "bidirectional"))
      (node (ref "U1") (pin "9") (pinfunction "IOB4_9") (pintype "bidirectional"))
    )
    (net (code "95") (name "Net-(U1-IOB5)") (class "Default")
      (node (ref "J4") (pin "P$4") (pinfunction "P$4_P$4") (pintype "bidirectional"))
      (node (ref "U1") (pin "8") (pinfunction "IOB5_8") (pintype "bidirectional"))
    )
    (net (code "96") (name "Net-(U1-IOB6)") (class "Default")
      (node (ref "J4") (pin "P$3") (pinfunction "P$3_P$3") (pintype "bidirectional"))
      (node (ref "U1") (pin "7") (pinfunction "IOB6_7") (pintype "bidirectional"))
    )
    (net (code "97") (name "Net-(U1-IOB7)") (class "Default")
      (node (ref "J4") (pin "P$2") (pinfunction "P$2_P$2") (pintype "bidirectional"))
      (node (ref "U1") (pin "6") (pinfunction "IOB7_6") (pintype "bidirectional"))
    )
    (net (code "98") (name "Net-(U4A-D)") (class "Default")
      (node (ref "U4") (pin "2") (pinfunction "D_2") (pintype "input"))
      (node (ref "U4") (pin "6") (pinfunction "~{Q}_6") (pintype "output"))
    )
    (net (code "99") (name "Net-(U5A-I4)") (class "Default")
      (node (ref "U5") (pin "5") (pinfunction "I4_5") (pintype "input"))
      (node (ref "U6") (pin "4") (pinfunction "O_4") (pintype "output"))
    )
    (net (code "100") (name "Net-(U5A-I5)") (class "Default")
      (node (ref "U5") (pin "6") (pinfunction "I5_6") (pintype "input"))
      (node (ref "U6") (pin "6") (pinfunction "O_6") (pintype "output"))
    )
    (net (code "101") (name "Net-(U5A-O)") (class "Default")
      (node (ref "U5") (pin "8") (pinfunction "O_8") (pintype "output"))
      (node (ref "U7") (pin "12") (pinfunction "I1_12") (pintype "input"))
      (node (ref "U7") (pin "2") (pinfunction "I0_2") (pintype "input"))
    )
    (net (code "102") (name "Net-(U6A-O)") (class "Default")
      (node (ref "U6") (pin "2") (pinfunction "O_2") (pintype "output"))
      (node (ref "U6") (pin "8") (pinfunction "O_8") (pintype "output"))
    )
    (net (code "103") (name "Net-(U6F-O)") (class "Default")
      (node (ref "U6") (pin "12") (pinfunction "O_12") (pintype "output"))
      (node (ref "U7") (pin "8") (pinfunction "I0_8") (pintype "input"))
    )
    (net (code "104") (name "Net-(U7C-O)") (class "Default")
      (node (ref "U7") (pin "10") (pinfunction "O_10") (pintype "output"))
      (node (ref "U7") (pin "11") (pinfunction "I0_11") (pintype "input"))
    )
    (net (code "105") (name "SND") (class "Default")
      (node (ref "J1") (pin "P$2") (pinfunction "X2_P$2") (pintype "bidirectional"))
      (node (ref "J2") (pin "P$2") (pinfunction "X2_P$2") (pintype "bidirectional"))
      (node (ref "Q1") (pin "1") (pinfunction "C_1") (pintype "passive"))
      (node (ref "XC1") (pin "P$2") (pinfunction "X2_P$2") (pintype "bidirectional"))
    )
    (net (code "106") (name "VCC") (class "Default")
      (node (ref "C1") (pin "1") (pinfunction "1_1") (pintype "passive"))
      (node (ref "C10") (pin "2") (pinfunction "2_2") (pintype "passive"))
      (node (ref "C2") (pin "2") (pinfunction "2_2") (pintype "passive"))
      (node (ref "C3") (pin "2") (pinfunction "2_2") (pintype "passive"))
      (node (ref "C4") (pin "2") (pinfunction "2_2") (pintype "passive"))
      (node (ref "C5") (pin "2") (pinfunction "2_2") (pintype "passive"))
      (node (ref "C6") (pin "2") (pinfunction "2_2") (pintype "passive"))
      (node (ref "C7") (pin "2") (pinfunction "2_2") (pintype "passive"))
      (node (ref "C8") (pin "+") (pinfunction "+_+") (pintype "passive"))
      (node (ref "C9") (pin "2") (pinfunction "2_2") (pintype "passive"))
      (node (ref "J1") (pin "P$25") (pinfunction "X25_P$25") (pintype "bidirectional"))
      (node (ref "J2") (pin "P$25") (pinfunction "X25_P$25") (pintype "bidirectional"))
      (node (ref "L1") (pin "1") (pinfunction "1_1") (pintype "passive"))
      (node (ref "L1") (pin "2") (pinfunction "2_2") (pintype "passive"))
      (node (ref "R1") (pin "2") (pinfunction "2_2") (pintype "passive"))
      (node (ref "U1") (pin "25") (pinfunction "A8_25") (pintype "bidirectional"))
      (node (ref "U1") (pin "28") (pinfunction "BC2_28") (pintype "bidirectional"))
      (node (ref "U1") (pin "40") (pinfunction "VCC_40") (pintype "power_in"))
      (node (ref "U4") (pin "1") (pinfunction "CLR_1") (pintype "input"))
      (node (ref "U4") (pin "4") (pinfunction "PRE_4") (pintype "input"))
      (node (ref "XC1") (pin "P$25") (pinfunction "X25_P$25") (pintype "bidirectional"))
      (node (ref "XX03") (pin "P$1") (pinfunction "P$1_P$1") (pintype "bidirectional"))
      (node (ref "XX03") (pin "P$2") (pinfunction "P$2_P$2") (pintype "bidirectional"))
    )
    (net (code "107") (name "unconnected-(U1-TST1-Pad39)") (class "Default")
      (node (ref "U1") (pin "39") (pinfunction "TST1_39") (pintype "bidirectional"))
    )
    (net (code "108") (name "unconnected-(U1-TST2-Pad26)") (class "Default")
      (node (ref "U1") (pin "26") (pinfunction "TST2_26") (pintype "bidirectional"))
    )
    (net (code "109") (name "unconnected-(U4B-CLK-Pad11)") (class "Default")
      (node (ref "U4") (pin "11") (pinfunction "CLK_11") (pintype "input"))
    )
    (net (code "110") (name "unconnected-(U4B-CLR-Pad13)") (class "Default")
      (node (ref "U4") (pin "13") (pinfunction "CLR_13") (pintype "input"))
    )
    (net (code "111") (name "unconnected-(U4B-D-Pad12)") (class "Default")
      (node (ref "U4") (pin "12") (pinfunction "D_12") (pintype "input"))
    )
    (net (code "112") (name "unconnected-(U4B-PRE-Pad10)") (class "Default")
      (node (ref "U4") (pin "10") (pinfunction "PRE_10") (pintype "input"))
    )
    (net (code "113") (name "unconnected-(U4B-Q-Pad9)") (class "Default")
      (node (ref "U4") (pin "9") (pinfunction "Q_9") (pintype "output"))
    )
    (net (code "114") (name "unconnected-(U4B-~{Q}-Pad8)") (class "Default")
      (node (ref "U4") (pin "8") (pinfunction "~{Q}_8") (pintype "output"))
    )
    (net (code "115") (name "unconnected-(U6A-I-Pad1)") (class "Default")
      (node (ref "U6") (pin "1") (pinfunction "I_1") (pintype "input"))
    )
    (net (code "116") (name "unconnected-(U6D-I-Pad9)") (class "Default")
      (node (ref "U6") (pin "9") (pinfunction "I_9") (pintype "input"))
    )
    (net (code "117") (name "unconnected-(U6E-I-Pad11)") (class "Default")
      (node (ref "U6") (pin "11") (pinfunction "I_11") (pintype "input"))
    )
    (net (code "118") (name "unconnected-(U6E-O-Pad10)") (class "Default")
      (node (ref "U6") (pin "10") (pinfunction "O_10") (pintype "output"))
    )
    (net (code "119") (name "unconnected-(U7B-I0-Pad5)") (class "Default")
      (node (ref "U7") (pin "5") (pinfunction "I0_5") (pintype "input"))
    )
    (net (code "120") (name "unconnected-(U7B-I1-Pad6)") (class "Default")
      (node (ref "U7") (pin "6") (pinfunction "I1_6") (pintype "input"))
    )
    (net (code "121") (name "unconnected-(U7B-O-Pad4)") (class "Default")
      (node (ref "U7") (pin "4") (pinfunction "O_4") (pintype "output"))
    )
    (net (code "122") (name "Φ") (class "Default")
      (node (ref "J1") (pin "P$8") (pinfunction "X8_P$8") (pintype "bidirectional"))
      (node (ref "J2") (pin "P$8") (pinfunction "X8_P$8") (pintype "bidirectional"))
      (node (ref "U4") (pin "3") (pinfunction "CLK_3") (pintype "input"))
      (node (ref "XC1") (pin "P$8") (pinfunction "X8_P$8") (pintype "bidirectional"))
    )
  )
)
